# Pi1541_HAT.net
KiCad netlist of a schematic drawn in EAGLE
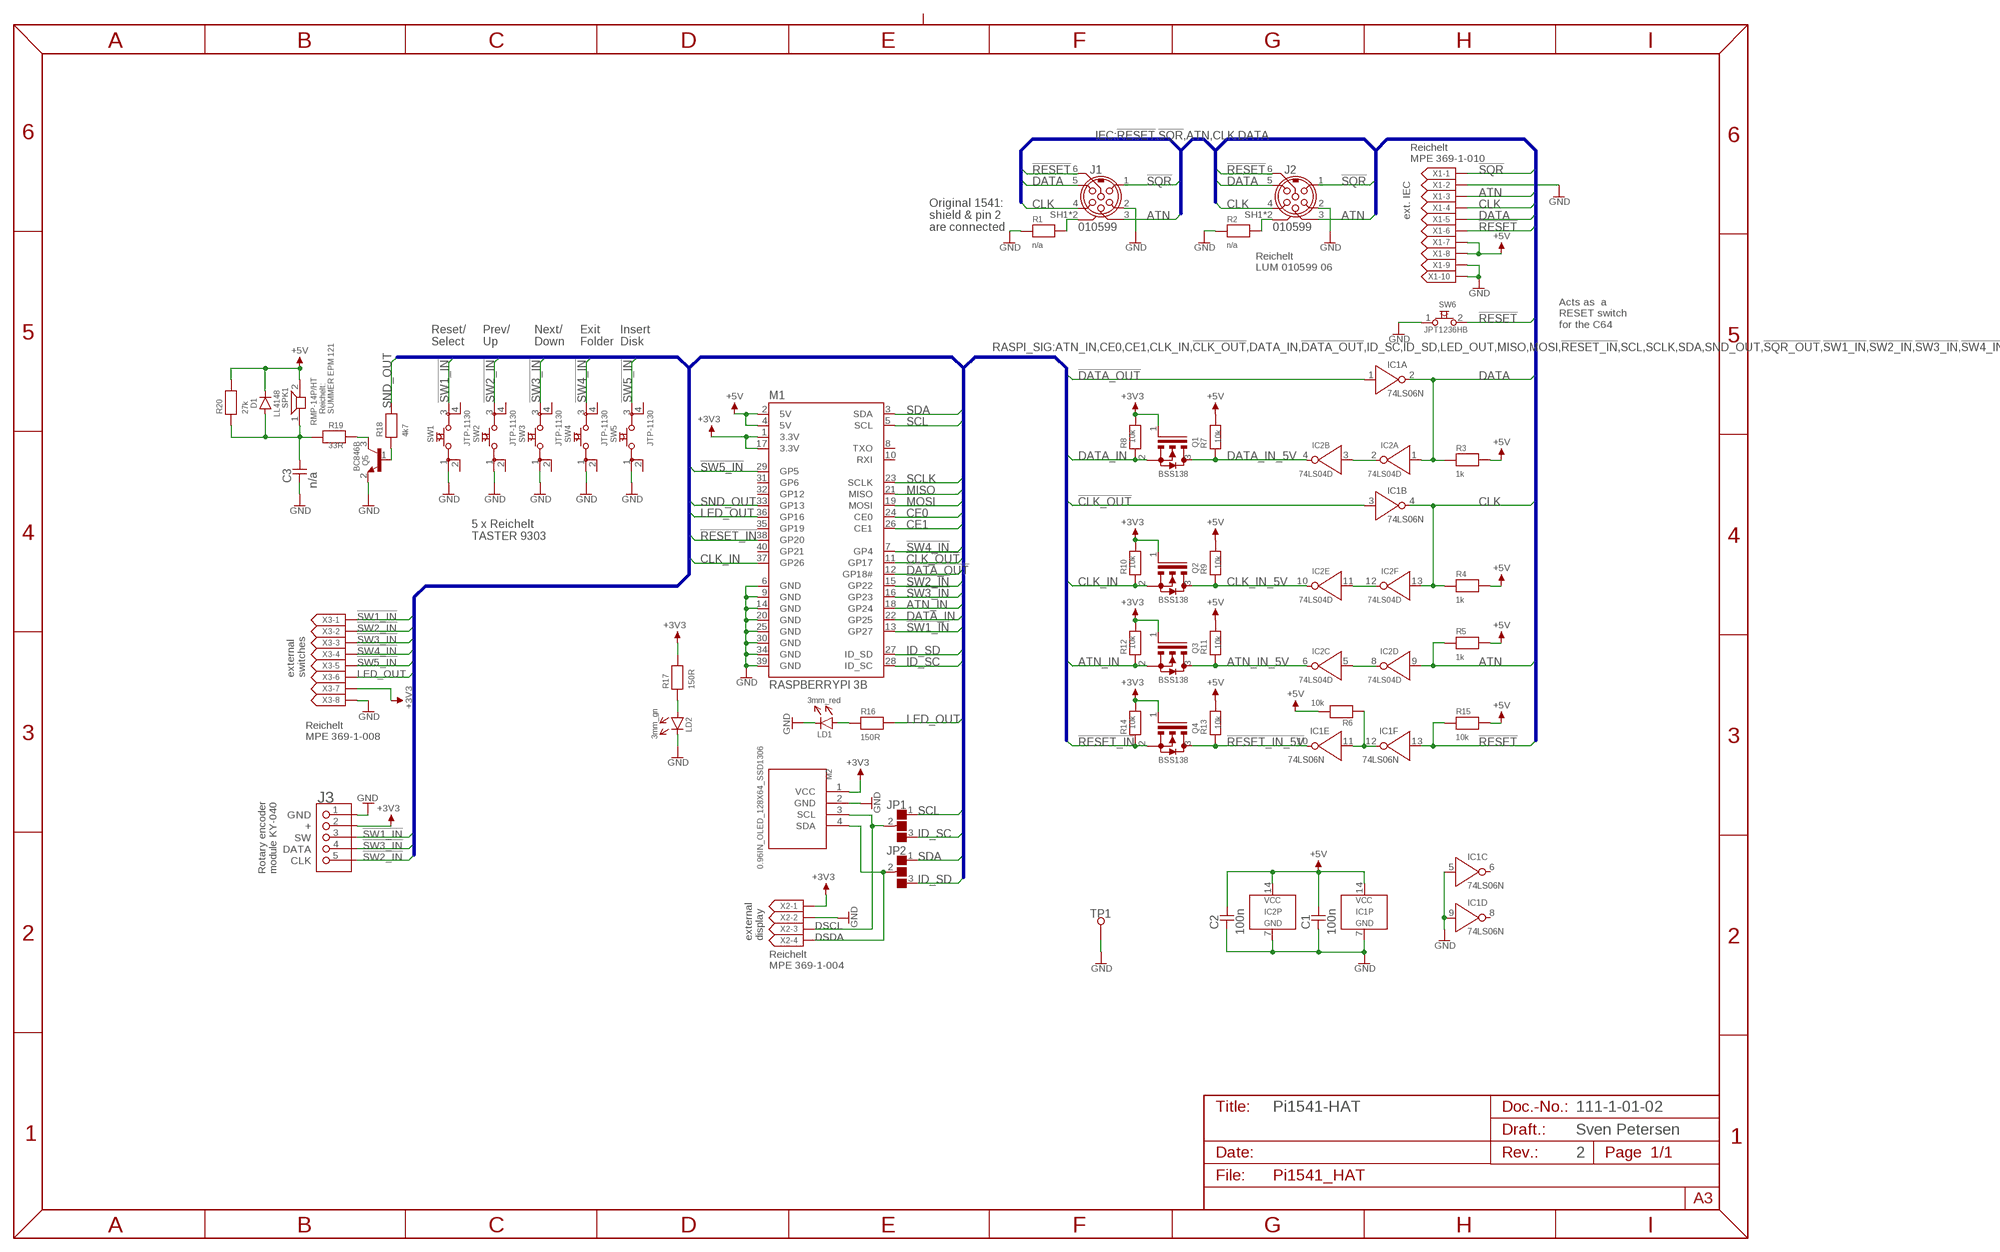
[diagram p0: schematic, sheet 1]

(export (version "E")
  (design (tool "Eeschema 10.0.6"))
  (components
    (comp (ref "C1")
      (value "100n")
      (footprint "eagle-import:0805")
      (libsource (lib "eagle-import") (part "C-0805"))
    )
    (comp (ref "C2")
      (value "100n")
      (footprint "eagle-import:0805")
      (libsource (lib "eagle-import") (part "C-0805"))
    )
    (comp (ref "C3")
      (value "n/a")
      (footprint "eagle-import:0805")
      (libsource (lib "eagle-import") (part "C-0805"))
    )
    (comp (ref "D1")
      (value "LL4148")
      (footprint "eagle-import:SOD80C")
      (libsource (lib "eagle-import") (part "LL4148"))
    )
    (comp (ref "IC1")
      (value "74LS06N")
      (footprint "eagle-import:DIL-14")
      (libsource (lib "eagle-import") (part "7406N"))
    )
    (comp (ref "IC2")
      (value "74LS04D")
      (footprint "eagle-import:SO-14")
      (libsource (lib "eagle-import") (part "7404HC"))
    )
    (comp (ref "J1")
      (value "010599")
      (footprint "eagle-import:010599")
      (libsource (lib "eagle-import") (part "010599"))
    )
    (comp (ref "J2")
      (value "010599")
      (footprint "eagle-import:010599")
      (libsource (lib "eagle-import") (part "010599"))
    )
    (comp (ref "J3")
      (value "PINHD-1X5")
      (footprint "eagle-import:1X05")
      (libsource (lib "eagle-import") (part "PINHD-1X5"))
    )
    (comp (ref "JP1")
      (value "JMP_0603")
      (footprint "eagle-import:CP3P")
      (libsource (lib "eagle-import") (part "JMP_0603"))
    )
    (comp (ref "JP2")
      (value "JMP_0603")
      (footprint "eagle-import:CP3P")
      (libsource (lib "eagle-import") (part "JMP_0603"))
    )
    (comp (ref "LD1")
      (value "3mm_red")
      (footprint "eagle-import:3MM")
      (libsource (lib "eagle-import") (part "3MM"))
    )
    (comp (ref "LD2")
      (value "3mm_gn")
      (footprint "eagle-import:3MM")
      (libsource (lib "eagle-import") (part "3MM"))
    )
    (comp (ref "M1")
      (value "RASPBERRYPI 3B")
      (footprint "eagle-import:PI_HAT_40P")
      (libsource (lib "eagle-import") (part "RASPBERRYPI-40-PIN-GPIO"))
    )
    (comp (ref "M2")
      (value "0.96IN_OLED_128X64_SSD1306")
      (footprint "eagle-import:OLED_0.96_SSD1306")
      (libsource (lib "eagle-import") (part "0.96IN_OLED_128X64_SSD1306"))
    )
    (comp (ref "Q1")
      (value "BSS138")
      (footprint "eagle-import:SOT23")
      (libsource (lib "eagle-import") (part "BSS138"))
    )
    (comp (ref "Q2")
      (value "BSS138")
      (footprint "eagle-import:SOT23")
      (libsource (lib "eagle-import") (part "BSS138"))
    )
    (comp (ref "Q3")
      (value "BSS138")
      (footprint "eagle-import:SOT23")
      (libsource (lib "eagle-import") (part "BSS138"))
    )
    (comp (ref "Q4")
      (value "BSS138")
      (footprint "eagle-import:SOT23")
      (libsource (lib "eagle-import") (part "BSS138"))
    )
    (comp (ref "Q5")
      (value "BC846B")
      (footprint "eagle-import:SOT23")
      (libsource (lib "eagle-import") (part "BC846"))
    )
    (comp (ref "R1")
      (value "n/a")
      (footprint "eagle-import:0805")
      (libsource (lib "eagle-import") (part "R-0805"))
    )
    (comp (ref "R2")
      (value "n/a")
      (footprint "eagle-import:0805")
      (libsource (lib "eagle-import") (part "R-0805"))
    )
    (comp (ref "R3")
      (value "1k")
      (footprint "eagle-import:0805")
      (libsource (lib "eagle-import") (part "R-0805"))
    )
    (comp (ref "R4")
      (value "1k")
      (footprint "eagle-import:0805")
      (libsource (lib "eagle-import") (part "R-0805"))
    )
    (comp (ref "R5")
      (value "1k")
      (footprint "eagle-import:0805")
      (libsource (lib "eagle-import") (part "R-0805"))
    )
    (comp (ref "R6")
      (value "10k")
      (footprint "eagle-import:0805")
      (libsource (lib "eagle-import") (part "R-0805"))
    )
    (comp (ref "R7")
      (value "10k")
      (footprint "eagle-import:0805")
      (libsource (lib "eagle-import") (part "R-0805"))
    )
    (comp (ref "R8")
      (value "10k")
      (footprint "eagle-import:0805")
      (libsource (lib "eagle-import") (part "R-0805"))
    )
    (comp (ref "R9")
      (value "10k")
      (footprint "eagle-import:0805")
      (libsource (lib "eagle-import") (part "R-0805"))
    )
    (comp (ref "R10")
      (value "10k")
      (footprint "eagle-import:0805")
      (libsource (lib "eagle-import") (part "R-0805"))
    )
    (comp (ref "R11")
      (value "10k")
      (footprint "eagle-import:0805")
      (libsource (lib "eagle-import") (part "R-0805"))
    )
    (comp (ref "R12")
      (value "10k")
      (footprint "eagle-import:0805")
      (libsource (lib "eagle-import") (part "R-0805"))
    )
    (comp (ref "R13")
      (value "10k")
      (footprint "eagle-import:0805")
      (libsource (lib "eagle-import") (part "R-0805"))
    )
    (comp (ref "R14")
      (value "10k")
      (footprint "eagle-import:0805")
      (libsource (lib "eagle-import") (part "R-0805"))
    )
    (comp (ref "R15")
      (value "10k")
      (footprint "eagle-import:0805")
      (libsource (lib "eagle-import") (part "R-0805"))
    )
    (comp (ref "R16")
      (value "150R")
      (footprint "eagle-import:0805")
      (libsource (lib "eagle-import") (part "R-0805"))
    )
    (comp (ref "R17")
      (value "150R")
      (footprint "eagle-import:0805")
      (libsource (lib "eagle-import") (part "R-0805"))
    )
    (comp (ref "R18")
      (value "4k7")
      (footprint "eagle-import:0805")
      (libsource (lib "eagle-import") (part "R-0805"))
    )
    (comp (ref "R19")
      (value "33R")
      (footprint "eagle-import:0805")
      (libsource (lib "eagle-import") (part "R-0805"))
    )
    (comp (ref "R20")
      (value "27k")
      (footprint "eagle-import:0805")
      (libsource (lib "eagle-import") (part "R-0805"))
    )
    (comp (ref "SPK1")
      (value "RMP-14P/HT")
      (footprint "eagle-import:RMP-14P_HT")
      (libsource (lib "eagle-import") (part "RMP-14P/HT"))
    )
    (comp (ref "SW1")
      (value "JTP-1130")
      (footprint "eagle-import:JTP-1130")
      (libsource (lib "eagle-import") (part "JTP-1130"))
    )
    (comp (ref "SW2")
      (value "JTP-1130")
      (footprint "eagle-import:JTP-1130")
      (libsource (lib "eagle-import") (part "JTP-1130"))
    )
    (comp (ref "SW3")
      (value "JTP-1130")
      (footprint "eagle-import:JTP-1130")
      (libsource (lib "eagle-import") (part "JTP-1130"))
    )
    (comp (ref "SW4")
      (value "JTP-1130")
      (footprint "eagle-import:JTP-1130")
      (libsource (lib "eagle-import") (part "JTP-1130"))
    )
    (comp (ref "SW5")
      (value "JTP-1130")
      (footprint "eagle-import:JTP-1130")
      (libsource (lib "eagle-import") (part "JTP-1130"))
    )
    (comp (ref "SW6")
      (value "JPT1236HB")
      (footprint "eagle-import:JTP_1236HB")
      (libsource (lib "eagle-import") (part "JPT1236HB"))
    )
    (comp (ref "TP1")
      (value "L1,2_R")
      (footprint "eagle-import:1,2MM_R")
      (libsource (lib "eagle-import") (part "L1,2_R"))
    )
    (comp (ref "X1")
      (value "369-1-010")
      (footprint "eagle-import:MICMA10B")
      (libsource (lib "eagle-import") (part "MICMA10B-THT"))
    )
    (comp (ref "X2")
      (value "369-1-004")
      (footprint "eagle-import:MICMA04B")
      (libsource (lib "eagle-import") (part "MICMA04B-THR"))
    )
    (comp (ref "X3")
      (value "369-1-008")
      (footprint "eagle-import:MICMA08B")
      (libsource (lib "eagle-import") (part "MICMA08B"))
    )
  )
  (nets
    (net (code "4") (name "+3V3") (class "Default")
      (node (ref "J3") (pin "2") (pinfunction "2_2") (pintype "passive"))
      (node (ref "M1") (pin "1") (pinfunction "3.3V_1") (pintype "power_in"))
      (node (ref "M1") (pin "17") (pinfunction "3.3V_17") (pintype "power_in"))
      (node (ref "M2") (pin "1") (pinfunction "VCC_1") (pintype "power_in"))
      (node (ref "Q1") (pin "1") (pinfunction "G_1") (pintype "bidirectional"))
      (node (ref "Q2") (pin "1") (pinfunction "G_1") (pintype "bidirectional"))
      (node (ref "Q3") (pin "1") (pinfunction "G_1") (pintype "bidirectional"))
      (node (ref "Q4") (pin "1") (pinfunction "G_1") (pintype "bidirectional"))
      (node (ref "R10") (pin "2") (pinfunction "2_2") (pintype "passive"))
      (node (ref "R12") (pin "2") (pinfunction "2_2") (pintype "passive"))
      (node (ref "R14") (pin "2") (pinfunction "2_2") (pintype "passive"))
      (node (ref "R17") (pin "2") (pinfunction "2_2") (pintype "passive"))
      (node (ref "R8") (pin "2") (pinfunction "2_2") (pintype "passive"))
      (node (ref "X2") (pin "1") (pinfunction "1_1") (pintype "bidirectional"))
      (node (ref "X3") (pin "7") (pinfunction "1_7") (pintype "bidirectional"))
    )
    (net (code "5") (name "+5V") (class "Default")
      (node (ref "C1") (pin "2") (pinfunction "2_2") (pintype "passive"))
      (node (ref "C2") (pin "2") (pinfunction "2_2") (pintype "passive"))
      (node (ref "D1") (pin "K") (pinfunction "K_K") (pintype "passive"))
      (node (ref "IC1") (pin "14") (pinfunction "VCC_14") (pintype "bidirectional"))
      (node (ref "IC2") (pin "14") (pinfunction "VCC_14") (pintype "bidirectional"))
      (node (ref "M1") (pin "2") (pinfunction "5V_2") (pintype "power_in"))
      (node (ref "M1") (pin "4") (pinfunction "5V_4") (pintype "power_in"))
      (node (ref "R11") (pin "2") (pinfunction "2_2") (pintype "passive"))
      (node (ref "R13") (pin "2") (pinfunction "2_2") (pintype "passive"))
      (node (ref "R15") (pin "2") (pinfunction "2_2") (pintype "passive"))
      (node (ref "R20") (pin "2") (pinfunction "2_2") (pintype "passive"))
      (node (ref "R3") (pin "2") (pinfunction "2_2") (pintype "passive"))
      (node (ref "R4") (pin "2") (pinfunction "2_2") (pintype "passive"))
      (node (ref "R5") (pin "2") (pinfunction "2_2") (pintype "passive"))
      (node (ref "R6") (pin "2") (pinfunction "2_2") (pintype "passive"))
      (node (ref "R7") (pin "2") (pinfunction "2_2") (pintype "passive"))
      (node (ref "R9") (pin "2") (pinfunction "2_2") (pintype "passive"))
      (node (ref "SPK1") (pin "2") (pinfunction "2_2") (pintype "bidirectional"))
      (node (ref "X1") (pin "7") (pinfunction "1_7") (pintype "bidirectional"))
      (node (ref "X1") (pin "8") (pinfunction "1_8") (pintype "bidirectional"))
    )
    (net (code "6") (name "/ATN") (class "Default")
      (node (ref "IC2") (pin "9") (pinfunction "I_9") (pintype "input"))
      (node (ref "J1") (pin "3") (pinfunction "3_3") (pintype "bidirectional"))
      (node (ref "J2") (pin "3") (pinfunction "3_3") (pintype "bidirectional"))
      (node (ref "R5") (pin "1") (pinfunction "1_1") (pintype "passive"))
      (node (ref "X1") (pin "3") (pinfunction "1_3") (pintype "bidirectional"))
    )
    (net (code "7") (name "/ATN_IN") (class "Default")
      (node (ref "M1") (pin "18") (pinfunction "GP24_18") (pintype "bidirectional"))
      (node (ref "Q3") (pin "2") (pinfunction "S_2") (pintype "bidirectional"))
      (node (ref "R12") (pin "1") (pinfunction "1_1") (pintype "passive"))
    )
    (net (code "8") (name "/ATN_IN_5V") (class "Default")
      (node (ref "IC2") (pin "6") (pinfunction "O_6") (pintype "output"))
      (node (ref "Q3") (pin "3") (pinfunction "D_3") (pintype "bidirectional"))
      (node (ref "R11") (pin "1") (pinfunction "1_1") (pintype "passive"))
    )
    (net (code "9") (name "/CE0") (class "Default")
      (node (ref "M1") (pin "24") (pinfunction "CE0_24") (pintype "output"))
    )
    (net (code "10") (name "/CE1") (class "Default")
      (node (ref "M1") (pin "26") (pinfunction "CE1_26") (pintype "output"))
    )
    (net (code "11") (name "/CLK") (class "Default")
      (node (ref "IC1") (pin "4") (pinfunction "O_4") (pintype "open_collector"))
      (node (ref "IC2") (pin "13") (pinfunction "I_13") (pintype "input"))
      (node (ref "J1") (pin "4") (pinfunction "4_4") (pintype "bidirectional"))
      (node (ref "J2") (pin "4") (pinfunction "4_4") (pintype "bidirectional"))
      (node (ref "R4") (pin "1") (pinfunction "1_1") (pintype "passive"))
      (node (ref "X1") (pin "4") (pinfunction "1_4") (pintype "bidirectional"))
    )
    (net (code "12") (name "/CLK_IN") (class "Default")
      (node (ref "M1") (pin "37") (pinfunction "GP26_37") (pintype "bidirectional"))
      (node (ref "Q2") (pin "2") (pinfunction "S_2") (pintype "bidirectional"))
      (node (ref "R10") (pin "1") (pinfunction "1_1") (pintype "passive"))
    )
    (net (code "13") (name "/CLK_IN_5V") (class "Default")
      (node (ref "IC2") (pin "10") (pinfunction "O_10") (pintype "output"))
      (node (ref "Q2") (pin "3") (pinfunction "D_3") (pintype "bidirectional"))
      (node (ref "R9") (pin "1") (pinfunction "1_1") (pintype "passive"))
    )
    (net (code "14") (name "/DATA") (class "Default")
      (node (ref "IC1") (pin "2") (pinfunction "O_2") (pintype "open_collector"))
      (node (ref "IC2") (pin "1") (pinfunction "I_1") (pintype "input"))
      (node (ref "J1") (pin "5") (pinfunction "5_5") (pintype "bidirectional"))
      (node (ref "J2") (pin "5") (pinfunction "5_5") (pintype "bidirectional"))
      (node (ref "R3") (pin "1") (pinfunction "1_1") (pintype "passive"))
      (node (ref "X1") (pin "5") (pinfunction "1_5") (pintype "bidirectional"))
    )
    (net (code "15") (name "/DATA_IN") (class "Default")
      (node (ref "M1") (pin "22") (pinfunction "GP25_22") (pintype "bidirectional"))
      (node (ref "Q1") (pin "2") (pinfunction "S_2") (pintype "bidirectional"))
      (node (ref "R8") (pin "1") (pinfunction "1_1") (pintype "passive"))
    )
    (net (code "16") (name "/DATA_IN_5V") (class "Default")
      (node (ref "IC2") (pin "4") (pinfunction "O_4") (pintype "output"))
      (node (ref "Q1") (pin "3") (pinfunction "D_3") (pintype "bidirectional"))
      (node (ref "R7") (pin "1") (pinfunction "1_1") (pintype "passive"))
    )
    (net (code "17") (name "/DSCL") (class "Default")
      (node (ref "JP1") (pin "2") (pinfunction "2_2") (pintype "bidirectional"))
      (node (ref "M2") (pin "3") (pinfunction "SCL_3") (pintype "input"))
      (node (ref "X2") (pin "3") (pinfunction "1_3") (pintype "bidirectional"))
    )
    (net (code "18") (name "/DSDA") (class "Default")
      (node (ref "JP2") (pin "2") (pinfunction "2_2") (pintype "bidirectional"))
      (node (ref "M2") (pin "4") (pinfunction "SDA_4") (pintype "bidirectional"))
      (node (ref "X2") (pin "4") (pinfunction "1_4") (pintype "bidirectional"))
    )
    (net (code "19") (name "/ID_SC") (class "Default")
      (node (ref "JP1") (pin "3") (pinfunction "3_3") (pintype "bidirectional"))
      (node (ref "M1") (pin "28") (pinfunction "ID_SC_28") (pintype "bidirectional"))
    )
    (net (code "20") (name "/ID_SD") (class "Default")
      (node (ref "JP2") (pin "3") (pinfunction "3_3") (pintype "bidirectional"))
      (node (ref "M1") (pin "27") (pinfunction "ID_SD_27") (pintype "bidirectional"))
    )
    (net (code "21") (name "/LED_OUT") (class "Default")
      (node (ref "M1") (pin "36") (pinfunction "GP16_36") (pintype "bidirectional"))
      (node (ref "R16") (pin "2") (pinfunction "2_2") (pintype "passive"))
      (node (ref "X3") (pin "6") (pinfunction "1_6") (pintype "bidirectional"))
    )
    (net (code "22") (name "/MISO") (class "Default")
      (node (ref "M1") (pin "21") (pinfunction "MISO_21") (pintype "input"))
    )
    (net (code "23") (name "/MOSI") (class "Default")
      (node (ref "M1") (pin "19") (pinfunction "MOSI_19") (pintype "output"))
    )
    (net (code "24") (name "/SCL") (class "Default")
      (node (ref "JP1") (pin "1") (pinfunction "1_1") (pintype "bidirectional"))
      (node (ref "M1") (pin "5") (pinfunction "SCL_5") (pintype "bidirectional"))
    )
    (net (code "25") (name "/SCLK") (class "Default")
      (node (ref "M1") (pin "23") (pinfunction "SCLK_23") (pintype "output"))
    )
    (net (code "26") (name "/SDA") (class "Default")
      (node (ref "JP2") (pin "1") (pinfunction "1_1") (pintype "bidirectional"))
      (node (ref "M1") (pin "3") (pinfunction "SDA_3") (pintype "bidirectional"))
    )
    (net (code "27") (name "/SND_OUT") (class "Default")
      (node (ref "M1") (pin "33") (pinfunction "GP13_33") (pintype "bidirectional"))
      (node (ref "R18") (pin "2") (pinfunction "2_2") (pintype "passive"))
    )
    (net (code "30") (name "/~{CLK_OUT}") (class "Default")
      (node (ref "IC1") (pin "3") (pinfunction "I_3") (pintype "input"))
      (node (ref "M1") (pin "11") (pinfunction "GP17_11") (pintype "bidirectional"))
    )
    (net (code "31") (name "/~{DATA_OUT}") (class "Default")
      (node (ref "IC1") (pin "1") (pinfunction "I_1") (pintype "input"))
      (node (ref "M1") (pin "12") (pinfunction "GP18#_12") (pintype "bidirectional"))
    )
    (net (code "32") (name "/~{RESET_IN_5V}") (class "Default")
      (node (ref "IC1") (pin "10") (pinfunction "O_10") (pintype "open_collector"))
      (node (ref "Q4") (pin "3") (pinfunction "D_3") (pintype "bidirectional"))
      (node (ref "R13") (pin "1") (pinfunction "1_1") (pintype "passive"))
    )
    (net (code "33") (name "/~{RESET_IN}") (class "Default")
      (node (ref "M1") (pin "38") (pinfunction "GP20_38") (pintype "bidirectional"))
      (node (ref "Q4") (pin "2") (pinfunction "S_2") (pintype "bidirectional"))
      (node (ref "R14") (pin "1") (pinfunction "1_1") (pintype "passive"))
    )
    (net (code "34") (name "/~{RESET}") (class "Default")
      (node (ref "IC1") (pin "13") (pinfunction "I_13") (pintype "input"))
      (node (ref "J1") (pin "6") (pinfunction "6_6") (pintype "bidirectional"))
      (node (ref "J2") (pin "6") (pinfunction "6_6") (pintype "bidirectional"))
      (node (ref "R15") (pin "1") (pinfunction "1_1") (pintype "passive"))
      (node (ref "SW6") (pin "2") (pinfunction "2_2") (pintype "passive"))
      (node (ref "X1") (pin "6") (pinfunction "1_6") (pintype "bidirectional"))
    )
    (net (code "35") (name "/~{SQR}") (class "Default")
      (node (ref "J1") (pin "1") (pinfunction "1_1") (pintype "bidirectional"))
      (node (ref "J2") (pin "1") (pinfunction "1_1") (pintype "bidirectional"))
      (node (ref "X1") (pin "1") (pinfunction "1_1") (pintype "bidirectional"))
    )
    (net (code "36") (name "/~{SW1_IN}") (class "Default")
      (node (ref "J3") (pin "3") (pinfunction "3_3") (pintype "passive"))
      (node (ref "M1") (pin "13") (pinfunction "GP27_13") (pintype "bidirectional"))
      (node (ref "SW1") (pin "3") (pinfunction "3_3") (pintype "passive"))
      (node (ref "X3") (pin "1") (pinfunction "1_1") (pintype "bidirectional"))
    )
    (net (code "37") (name "/~{SW2_IN}") (class "Default")
      (node (ref "J3") (pin "5") (pinfunction "5_5") (pintype "passive"))
      (node (ref "M1") (pin "15") (pinfunction "GP22_15") (pintype "bidirectional"))
      (node (ref "SW2") (pin "3") (pinfunction "3_3") (pintype "passive"))
      (node (ref "X3") (pin "2") (pinfunction "1_2") (pintype "bidirectional"))
    )
    (net (code "38") (name "/~{SW3_IN}") (class "Default")
      (node (ref "J3") (pin "4") (pinfunction "4_4") (pintype "passive"))
      (node (ref "M1") (pin "16") (pinfunction "GP23_16") (pintype "bidirectional"))
      (node (ref "SW3") (pin "3") (pinfunction "3_3") (pintype "passive"))
      (node (ref "X3") (pin "3") (pinfunction "1_3") (pintype "bidirectional"))
    )
    (net (code "39") (name "/~{SW4_IN}") (class "Default")
      (node (ref "M1") (pin "7") (pinfunction "GP4_7") (pintype "bidirectional"))
      (node (ref "SW4") (pin "3") (pinfunction "3_3") (pintype "passive"))
      (node (ref "X3") (pin "4") (pinfunction "1_4") (pintype "bidirectional"))
    )
    (net (code "40") (name "/~{SW5_IN}") (class "Default")
      (node (ref "M1") (pin "29") (pinfunction "GP5_29") (pintype "bidirectional"))
      (node (ref "SW5") (pin "3") (pinfunction "3_3") (pintype "passive"))
      (node (ref "X3") (pin "5") (pinfunction "1_5") (pintype "bidirectional"))
    )
    (net (code "41") (name "GND") (class "Default")
      (node (ref "C1") (pin "1") (pinfunction "1_1") (pintype "passive"))
      (node (ref "C2") (pin "1") (pinfunction "1_1") (pintype "passive"))
      (node (ref "C3") (pin "1") (pinfunction "1_1") (pintype "passive"))
      (node (ref "IC1") (pin "5") (pinfunction "I_5") (pintype "input"))
      (node (ref "IC1") (pin "7") (pinfunction "GND_7") (pintype "bidirectional"))
      (node (ref "IC1") (pin "9") (pinfunction "I_9") (pintype "input"))
      (node (ref "IC2") (pin "7") (pinfunction "GND_7") (pintype "bidirectional"))
      (node (ref "J1") (pin "2") (pinfunction "2_2") (pintype "bidirectional"))
      (node (ref "J2") (pin "2") (pinfunction "2_2") (pintype "bidirectional"))
      (node (ref "J3") (pin "1") (pinfunction "1_1") (pintype "passive"))
      (node (ref "LD1") (pin "K") (pinfunction "K_K") (pintype "bidirectional"))
      (node (ref "LD2") (pin "K") (pinfunction "K_K") (pintype "bidirectional"))
      (node (ref "M1") (pin "14") (pinfunction "GND_14") (pintype "power_in"))
      (node (ref "M1") (pin "20") (pinfunction "GND_20") (pintype "power_in"))
      (node (ref "M1") (pin "25") (pinfunction "GND_25") (pintype "power_in"))
      (node (ref "M1") (pin "30") (pinfunction "GND_30") (pintype "power_in"))
      (node (ref "M1") (pin "34") (pinfunction "GND_34") (pintype "power_in"))
      (node (ref "M1") (pin "39") (pinfunction "GND_39") (pintype "power_in"))
      (node (ref "M1") (pin "6") (pinfunction "GND_6") (pintype "power_in"))
      (node (ref "M1") (pin "9") (pinfunction "GND_9") (pintype "power_in"))
      (node (ref "M2") (pin "2") (pinfunction "GND_2") (pintype "power_in"))
      (node (ref "Q5") (pin "2") (pinfunction "E_2") (pintype "passive"))
      (node (ref "R1") (pin "1") (pinfunction "1_1") (pintype "passive"))
      (node (ref "R2") (pin "1") (pinfunction "1_1") (pintype "passive"))
      (node (ref "SW1") (pin "1") (pinfunction "1_1") (pintype "passive"))
      (node (ref "SW2") (pin "1") (pinfunction "1_1") (pintype "passive"))
      (node (ref "SW3") (pin "1") (pinfunction "1_1") (pintype "passive"))
      (node (ref "SW4") (pin "1") (pinfunction "1_1") (pintype "passive"))
      (node (ref "SW5") (pin "1") (pinfunction "1_1") (pintype "passive"))
      (node (ref "SW6") (pin "1") (pinfunction "1_1") (pintype "passive"))
      (node (ref "TP1") (pin "1") (pinfunction "1_1") (pintype "passive"))
      (node (ref "X1") (pin "10") (pinfunction "1_10") (pintype "bidirectional"))
      (node (ref "X1") (pin "2") (pinfunction "1_2") (pintype "bidirectional"))
      (node (ref "X1") (pin "9") (pinfunction "1_9") (pintype "bidirectional"))
      (node (ref "X2") (pin "2") (pinfunction "1_2") (pintype "bidirectional"))
      (node (ref "X3") (pin "8") (pinfunction "1_8") (pintype "bidirectional"))
    )
    (net (code "42") (name "Net-(C3-Pad2)") (class "Default")
      (node (ref "C3") (pin "2") (pinfunction "2_2") (pintype "passive"))
      (node (ref "D1") (pin "A") (pinfunction "A_A") (pintype "passive"))
      (node (ref "R19") (pin "1") (pinfunction "1_1") (pintype "passive"))
      (node (ref "R20") (pin "1") (pinfunction "1_1") (pintype "passive"))
      (node (ref "SPK1") (pin "1") (pinfunction "1_1") (pintype "bidirectional"))
    )
    (net (code "43") (name "Net-(IC1E-I)") (class "Default")
      (node (ref "IC1") (pin "11") (pinfunction "I_11") (pintype "input"))
      (node (ref "IC1") (pin "12") (pinfunction "O_12") (pintype "open_collector"))
      (node (ref "R6") (pin "1") (pinfunction "1_1") (pintype "passive"))
    )
    (net (code "44") (name "Net-(IC2A-O)") (class "Default")
      (node (ref "IC2") (pin "2") (pinfunction "O_2") (pintype "output"))
      (node (ref "IC2") (pin "3") (pinfunction "I_3") (pintype "input"))
    )
    (net (code "45") (name "Net-(IC2C-I)") (class "Default")
      (node (ref "IC2") (pin "5") (pinfunction "I_5") (pintype "input"))
      (node (ref "IC2") (pin "8") (pinfunction "O_8") (pintype "output"))
    )
    (net (code "46") (name "Net-(IC2E-I)") (class "Default")
      (node (ref "IC2") (pin "11") (pinfunction "I_11") (pintype "input"))
      (node (ref "IC2") (pin "12") (pinfunction "O_12") (pintype "output"))
    )
    (net (code "47") (name "Net-(J1-SH-PadSH1)") (class "Default")
      (node (ref "J1") (pin "SH1") (pinfunction "SH_SH1") (pintype "bidirectional"))
      (node (ref "J1") (pin "SH2") (pinfunction "SH_SH2") (pintype "bidirectional"))
      (node (ref "R1") (pin "2") (pinfunction "2_2") (pintype "passive"))
    )
    (net (code "48") (name "Net-(J2-SH-PadSH1)") (class "Default")
      (node (ref "J2") (pin "SH1") (pinfunction "SH_SH1") (pintype "bidirectional"))
      (node (ref "J2") (pin "SH2") (pinfunction "SH_SH2") (pintype "bidirectional"))
      (node (ref "R2") (pin "2") (pinfunction "2_2") (pintype "passive"))
    )
    (net (code "49") (name "Net-(LD1-PadA)") (class "Default")
      (node (ref "LD1") (pin "A") (pinfunction "A_A") (pintype "bidirectional"))
      (node (ref "R16") (pin "1") (pinfunction "1_1") (pintype "passive"))
    )
    (net (code "50") (name "Net-(LD2-PadA)") (class "Default")
      (node (ref "LD2") (pin "A") (pinfunction "A_A") (pintype "bidirectional"))
      (node (ref "R17") (pin "1") (pinfunction "1_1") (pintype "passive"))
    )
    (net (code "51") (name "Net-(Q5-B)") (class "Default")
      (node (ref "Q5") (pin "1") (pinfunction "B_1") (pintype "passive"))
      (node (ref "R18") (pin "1") (pinfunction "1_1") (pintype "passive"))
    )
    (net (code "52") (name "Net-(Q5-C)") (class "Default")
      (node (ref "Q5") (pin "3") (pinfunction "C_3") (pintype "passive"))
      (node (ref "R19") (pin "2") (pinfunction "2_2") (pintype "passive"))
    )
    (net (code "53") (name "unconnected-(IC1C-O-Pad6)") (class "Default")
      (node (ref "IC1") (pin "6") (pinfunction "O_6") (pintype "open_collector"))
    )
    (net (code "54") (name "unconnected-(IC1D-O-Pad8)") (class "Default")
      (node (ref "IC1") (pin "8") (pinfunction "O_8") (pintype "open_collector"))
    )
    (net (code "55") (name "unconnected-(M1-GP6-Pad31)") (class "Default")
      (node (ref "M1") (pin "31") (pinfunction "GP6_31") (pintype "bidirectional"))
    )
    (net (code "56") (name "unconnected-(M1-GP12-Pad32)") (class "Default")
      (node (ref "M1") (pin "32") (pinfunction "GP12_32") (pintype "bidirectional"))
    )
    (net (code "57") (name "unconnected-(M1-GP19-Pad35)") (class "Default")
      (node (ref "M1") (pin "35") (pinfunction "GP19_35") (pintype "bidirectional"))
    )
    (net (code "58") (name "unconnected-(M1-GP21-Pad40)") (class "Default")
      (node (ref "M1") (pin "40") (pinfunction "GP21_40") (pintype "bidirectional"))
    )
    (net (code "59") (name "unconnected-(M1-RXI-Pad10)") (class "Default")
      (node (ref "M1") (pin "10") (pinfunction "RXI_10") (pintype "input"))
    )
    (net (code "60") (name "unconnected-(M1-TXO-Pad8)") (class "Default")
      (node (ref "M1") (pin "8") (pinfunction "TXO_8") (pintype "output"))
    )
    (net (code "61") (name "unconnected-(SW1-Pad2)") (class "Default")
      (node (ref "SW1") (pin "2") (pinfunction "2_2") (pintype "passive"))
    )
    (net (code "62") (name "unconnected-(SW1-Pad4)") (class "Default")
      (node (ref "SW1") (pin "4") (pinfunction "4_4") (pintype "passive"))
    )
    (net (code "63") (name "unconnected-(SW2-Pad2)") (class "Default")
      (node (ref "SW2") (pin "2") (pinfunction "2_2") (pintype "passive"))
    )
    (net (code "64") (name "unconnected-(SW2-Pad4)") (class "Default")
      (node (ref "SW2") (pin "4") (pinfunction "4_4") (pintype "passive"))
    )
    (net (code "65") (name "unconnected-(SW3-Pad2)") (class "Default")
      (node (ref "SW3") (pin "2") (pinfunction "2_2") (pintype "passive"))
    )
    (net (code "66") (name "unconnected-(SW3-Pad4)") (class "Default")
      (node (ref "SW3") (pin "4") (pinfunction "4_4") (pintype "passive"))
    )
    (net (code "67") (name "unconnected-(SW4-Pad2)") (class "Default")
      (node (ref "SW4") (pin "2") (pinfunction "2_2") (pintype "passive"))
    )
    (net (code "68") (name "unconnected-(SW4-Pad4)") (class "Default")
      (node (ref "SW4") (pin "4") (pinfunction "4_4") (pintype "passive"))
    )
    (net (code "69") (name "unconnected-(SW5-Pad2)") (class "Default")
      (node (ref "SW5") (pin "2") (pinfunction "2_2") (pintype "passive"))
    )
    (net (code "70") (name "unconnected-(SW5-Pad4)") (class "Default")
      (node (ref "SW5") (pin "4") (pinfunction "4_4") (pintype "passive"))
    )
  )
)
